# PSU.net
KiCad netlist of a schematic drawn in Altium Designer
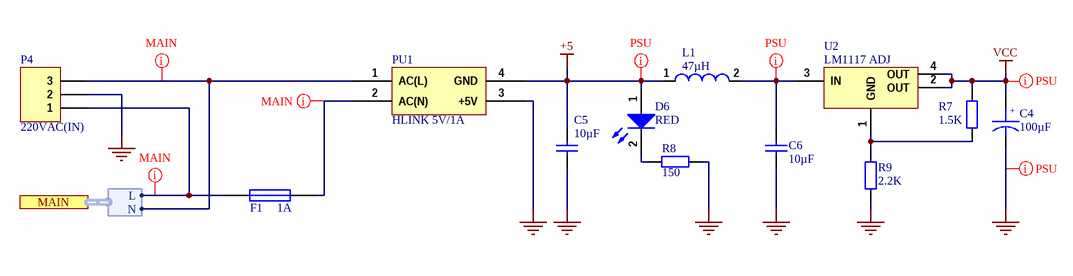
[diagram p0: PSU.SchDoc]

(export (version "E")
  (design (tool "Eeschema 10.0.6"))
  (components
    (comp (ref "C4")
      (value "100µF")
      (footprint "KEMET_4 - 3")
      (description "SMD Polarized Capacitor 16V")
      (fields
        (field (name "MANUFACTURER") "EPCOS")
        (field (name "MANUFACTURER PART NUMBER") "B41142A4107M")
        (field (name "HAUTEUR") "7.7")
        (field (name "LONGUEUR/HAUTEUR") "7.7")
      )
      (libsource (lib "BRA") (part "Cap Pol 100µF - 16"))
    )
    (comp (ref "C5")
      (value "10µF")
      (footprint "C 0805(2012)x0.65")
      (description "Capacitor non polarized 10µF SMD 0805")
      (fields (field (name "TOLERANCE") "10%") (field (name "VOLTAGE") "16V"))
      (libsource (lib "BRA") (part "Cap 0805 10µF"))
    )
    (comp (ref "C6")
      (value "10µF")
      (footprint "C 0805(2012)x0.65")
      (description "Capacitor non polarized 10µF SMD 0805")
      (fields (field (name "TOLERANCE") "10%") (field (name "VOLTAGE") "16V"))
      (libsource (lib "BRA") (part "Cap 0805 10µF"))
    )
    (comp (ref "D6")
      (value "RED")
      (footprint "0603-LEDR")
      (description "Surface Mount Chip LED, Red")
      (fields
        (field (name "MANUFACTURER") "AVAGO TECHNOLOGIES")
        (field (name "MANUFACTURER PART NUMBER") "HSMH-C190.")
        (field (name "LONGUEUR/HAUTEUR") "1.6")
      )
      (libsource (lib "BRA") (part "HSMH-C190"))
    )
    (comp (ref "F1")
      (value "1A")
      (footprint "FUS5X20")
      (description "Fuse holder 5x20 SMD")
      (fields
        (field (name "MANUFACTURER") "LITTELFUSE WICKMANN")
        (field (name "MANUFACTURER PART NUMBER") "65800001009")
      )
      (libsource (lib "BRA") (part "Fuse holder SMD 5X20"))
    )
    (comp (ref "L1")
      (value "47µH")
      (footprint "SELF4.5X4X3.2")
      (fields
        (field (name "MANUFACTURER") "COILCRAFT")
        (field (name "MANUFACTURER PART NUMBER") "DO3316P-473MLD")
      )
      (libsource (lib "UTIL_Library") (part "SELF"))
    )
    (comp (ref "P4")
      (value "220VAC(IN)")
      (footprint "CO3P508 - 2")
      (description "Header, 3-Pin")
      (fields
        (field (name "MANUFACTURER") "TE CONNECTIVITY / BUCHANAN")
        (field (name "MANUFACTURER PART NUMBER") "796636-3")
        (field (name "PUBLISHER") "Altium Limited")
      )
      (libsource (lib "BRA") (part "Header 3"))
    )
    (comp (ref "PU1")
      (value "HLINK 5V/1A")
      (footprint "H-LINK")
      (description "POWER SUPPLY 5V 1A")
      (libsource (lib "BRA") (part "H-LINK  5"))
    )
    (comp (ref "R7")
      (value "1.5K")
      (footprint "R 0805(2012)")
      (description "Resistor SMD 0805 1.5K")
      (fields (field (name "TOLERANCE") "1%"))
      (libsource (lib "BRA") (part "Resistor 0805 1.5K"))
    )
    (comp (ref "R8")
      (value "150")
      (footprint "R 0805(2012)")
      (description "Resistor SMD 0805 150")
      (fields
        (field (name "MANUFACTURER") "YAGEO")
        (field (name "MANUFACTURER PART NUMBER") "RC0805JR-07150KL")
      )
      (libsource (lib "BRA") (part "Resistor 0805 150"))
    )
    (comp (ref "R9")
      (value "2.2K")
      (footprint "R 0805(2012)")
      (description "Resistor SMD 0805 2.2K")
      (fields
        (field (name "MANUFACTURER") "BOURNS")
        (field (name "MANUFACTURER PART NUMBER") "CR0805-FX-2201ELF")
      )
      (libsource (lib "BRA") (part "Resistor 0805 2.2K"))
    )
    (comp (ref "U2")
      (value "LM1117 ADJ")
      (footprint "SOT223")
      (description "800mA Adjustable low-Dropout Linear Regulator, 3-pin TO-252")
      (libsource (lib "BRA") (part "LM1117DT-ADJ"))
    )
  )
  (nets
    (net (code "2") (name "+5") (class "Default")
      (node (ref "C5") (pin "1") (pinfunction "1_1") (pintype "passive"))
      (node (ref "D6") (pin "1") (pinfunction "A_1") (pintype "passive"))
      (node (ref "L1") (pin "1") (pinfunction "1_1") (pintype "passive"))
      (node (ref "PU1") (pin "4") (pinfunction "GND_4") (pintype "power_in"))
    )
    (net (code "4") (name "GND") (class "Default")
      (node (ref "C4") (pin "2") (pinfunction "2_2") (pintype "passive"))
      (node (ref "C5") (pin "2") (pinfunction "2_2") (pintype "passive"))
      (node (ref "C6") (pin "2") (pinfunction "2_2") (pintype "passive"))
      (node (ref "P4") (pin "2") (pinfunction "2_2") (pintype "passive"))
      (node (ref "PU1") (pin "3") (pinfunction "+5V_3") (pintype "power_in"))
      (node (ref "R8") (pin "1") (pinfunction "1_1") (pintype "passive"))
      (node (ref "R9") (pin "1") (pinfunction "1_1") (pintype "passive"))
    )
    (net (code "5") (name "Net-(D6-K)") (class "Default")
      (node (ref "D6") (pin "2") (pinfunction "K_2") (pintype "passive"))
      (node (ref "R8") (pin "2") (pinfunction "2_2") (pintype "passive"))
    )
    (net (code "6") (name "Net-(F1-Pad1)") (class "Default")
      (node (ref "F1") (pin "1") (pinfunction "1_1") (pintype "passive"))
      (node (ref "P4") (pin "1") (pinfunction "1_1") (pintype "passive"))
    )
    (net (code "7") (name "Net-(PU1-AC(L))") (class "Default")
      (node (ref "P4") (pin "3") (pinfunction "3_3") (pintype "passive"))
      (node (ref "PU1") (pin "1") (pinfunction "AC(L)_1") (pintype "passive"))
    )
    (net (code "8") (name "Net-(PU1-AC(N))") (class "Default")
      (node (ref "F1") (pin "2") (pinfunction "2_2") (pintype "passive"))
      (node (ref "PU1") (pin "2") (pinfunction "AC(N)_2") (pintype "power_in"))
    )
    (net (code "9") (name "Net-(U2-GND)") (class "Default")
      (node (ref "R7") (pin "1") (pinfunction "1_1") (pintype "passive"))
      (node (ref "R9") (pin "2") (pinfunction "2_2") (pintype "passive"))
      (node (ref "U2") (pin "1") (pinfunction "GND_1") (pintype "power_in"))
    )
    (net (code "10") (name "Net-(U2-IN)") (class "Default")
      (node (ref "C6") (pin "1") (pinfunction "1_1") (pintype "passive"))
      (node (ref "L1") (pin "2") (pinfunction "2_2") (pintype "passive"))
      (node (ref "U2") (pin "3") (pinfunction "IN_3") (pintype "power_in"))
    )
    (net (code "11") (name "VCC") (class "Default")
      (node (ref "C4") (pin "1") (pinfunction "1_1") (pintype "passive"))
      (node (ref "R7") (pin "2") (pinfunction "2_2") (pintype "passive"))
      (node (ref "U2") (pin "2") (pinfunction "OUT_2") (pintype "power_in"))
      (node (ref "U2") (pin "4") (pinfunction "OUT_4") (pintype "power_in"))
    )
  )
)
